# Power_Supply.net
KiCad netlist of a schematic drawn in Altium Designer
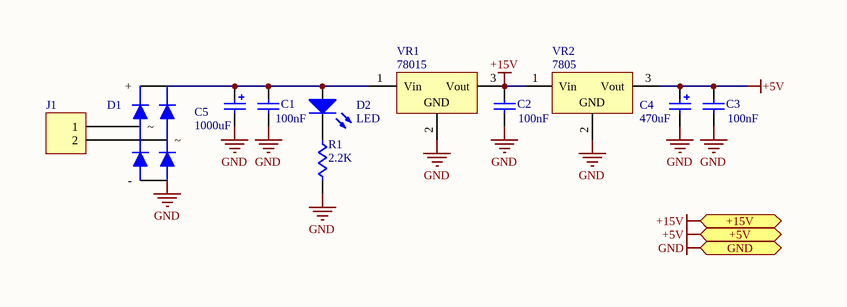
[diagram p0: Power Supply.SchDoc]

(export (version "E")
  (design (tool "Eeschema 10.0.6"))
  (components
    (comp (ref "C1")
      (value "100nF")
      (footprint "CAPNTO2.54-3.05x1.78A")
      (description "Capacitor")
      (fields
        (field (name "MANUFACTURER") "Generic Components")
        (field (name "Comment") "Cap")
        (field (name "PUBLISHER") "Altium Limited")
      )
      (libsource (lib "Miscellaneous Devices") (part "Cap"))
    )
    (comp (ref "C2")
      (value "100nF")
      (footprint "CAPNTO2.54-3.05x1.78A")
      (description "Capacitor")
      (fields
        (field (name "MANUFACTURER") "Generic Components")
        (field (name "Comment") "Cap")
        (field (name "PUBLISHER") "Altium Limited")
      )
      (libsource (lib "Miscellaneous Devices") (part "Cap"))
    )
    (comp (ref "C3")
      (value "100nF")
      (footprint "CAPNTO2.54-3.05x1.78A")
      (description "Capacitor")
      (fields
        (field (name "MANUFACTURER") "Generic Components")
        (field (name "Comment") "Cap")
        (field (name "PUBLISHER") "Altium Limited")
      )
      (libsource (lib "Miscellaneous Devices") (part "Cap"))
    )
    (comp (ref "C4")
      (value "470uF")
      (footprint "CAPPR3.05-3.81x6.35")
      (description "Polarized Capacitor (Radial)")
      (fields
        (field (name "MANUFACTURER") "Generic Components")
        (field (name "Comment") "Cap Pol1")
        (field (name "PUBLISHER") "Altium Limited")
      )
      (libsource (lib "Miscellaneous Devices") (part "Cap Pol1"))
    )
    (comp (ref "C5")
      (value "1000uF")
      (footprint "CAPPR5-10x12.5")
      (description "Polarized Capacitor (Radial)")
      (fields
        (field (name "MANUFACTURER") "Generic Components")
        (field (name "Comment") "Cap Pol1")
        (field (name "PUBLISHER") "Altium Limited")
      )
      (libsource (lib "Miscellaneous Devices") (part "Cap Pol1"))
    )
    (comp (ref "D1")
      (value "Bridge_1")
      (footprint "KBP")
      (description "Full Wave Diode Bridge")
      (fields (field (name "MANUFACTURER") "Generic Components") (field (name "PUBLISHER") "Altium Limited"))
      (libsource (lib "my Libraries") (part "Bridge_1"))
    )
    (comp (ref "D2")
      (value "LED")
      (footprint "LED-5mm_Red")
      (description "Typical INFRARED GaAs LED")
      (fields (field (name "MANUFACTURER") "Generic Components") (field (name "PUBLISHER") "Altium Limited"))
      (libsource (lib "Miscellaneous Devices") (part "LED"))
    )
    (comp (ref "J1")
      (value "Header 2")
      (footprint "Fonics_2PIN_1")
      (description "Header, 2-Pin")
      (fields (field (name "PUBLISHER") "Altium Limited"))
      (libsource (lib "Miscellaneous Connectors") (part "Header 2"))
    )
    (comp (ref "R1")
      (value "2.2K")
      (footprint "AXIAL-0.4")
      (description "Resistor")
      (fields
        (field (name "MANUFACTURER") "Generic Components")
        (field (name "Comment") "Res1")
        (field (name "PUBLISHER") "Altium Limited")
      )
      (libsource (lib "Miscellaneous Devices") (part "Res1"))
    )
    (comp (ref "VR1")
      (value "78015")
      (footprint "TO220V")
      (description "Voltage Regulator")
      (fields
        (field (name "MANUFACTURER") "Generic Components")
        (field (name "Comment") "Volt Reg")
        (field (name "PUBLISHER") "Altium Limited")
      )
      (libsource (lib "my Libraries") (part "Volt Reg"))
    )
    (comp (ref "VR2")
      (value "7805")
      (footprint "TO220V")
      (description "Voltage Regulator")
      (fields
        (field (name "MANUFACTURER") "Generic Components")
        (field (name "Comment") "Volt Reg")
        (field (name "PUBLISHER") "Altium Limited")
      )
      (libsource (lib "my Libraries") (part "Volt Reg"))
    )
  )
  (nets
    (net (code "1") (name "+5V") (class "Default")
      (node (ref "C3") (pin "2") (pinfunction "2_2") (pintype "passive"))
      (node (ref "C4") (pin "1") (pinfunction "1_1") (pintype "passive"))
      (node (ref "VR2") (pin "3") (pinfunction "Vout_3") (pintype "passive"))
    )
    (net (code "2") (name "+15V") (class "Default")
      (node (ref "C2") (pin "2") (pinfunction "2_2") (pintype "passive"))
      (node (ref "VR1") (pin "3") (pinfunction "Vout_3") (pintype "passive"))
      (node (ref "VR2") (pin "1") (pinfunction "Vin_1") (pintype "passive"))
    )
    (net (code "3") (name "GND") (class "Default")
      (node (ref "C1") (pin "1") (pinfunction "1_1") (pintype "passive"))
      (node (ref "C2") (pin "1") (pinfunction "1_1") (pintype "passive"))
      (node (ref "C3") (pin "1") (pinfunction "1_1") (pintype "passive"))
      (node (ref "C4") (pin "2") (pinfunction "2_2") (pintype "passive"))
      (node (ref "C5") (pin "2") (pinfunction "2_2") (pintype "passive"))
      (node (ref "D1") (pin "1") (pinfunction "-_1") (pintype "passive"))
      (node (ref "R1") (pin "2") (pinfunction "2_2") (pintype "passive"))
      (node (ref "VR1") (pin "2") (pinfunction "GND_2") (pintype "passive"))
      (node (ref "VR2") (pin "2") (pinfunction "GND_2") (pintype "passive"))
    )
    (net (code "4") (name "Net-(D1-+)") (class "Default")
      (node (ref "C1") (pin "2") (pinfunction "2_2") (pintype "passive"))
      (node (ref "C5") (pin "1") (pinfunction "1_1") (pintype "passive"))
      (node (ref "D1") (pin "3") (pinfunction "+_3") (pintype "passive"))
      (node (ref "D2") (pin "1") (pinfunction "A_1") (pintype "passive"))
      (node (ref "VR1") (pin "1") (pinfunction "Vin_1") (pintype "passive"))
    )
    (net (code "5") (name "Net-(D1-~-Pad2)") (class "Default")
      (node (ref "D1") (pin "2") (pinfunction "~_2") (pintype "passive"))
      (node (ref "J1") (pin "2") (pinfunction "2_2") (pintype "passive"))
    )
    (net (code "6") (name "Net-(D1-~-Pad4)") (class "Default")
      (node (ref "D1") (pin "4") (pinfunction "~_4") (pintype "passive"))
      (node (ref "J1") (pin "1") (pinfunction "1_1") (pintype "passive"))
    )
    (net (code "7") (name "Net-(D2-K)") (class "Default")
      (node (ref "D2") (pin "2") (pinfunction "K_2") (pintype "passive"))
      (node (ref "R1") (pin "1") (pinfunction "1_1") (pintype "passive"))
    )
  )
)
